# open-bldc.net
KiCad netlist of a schematic drawn in EAGLE
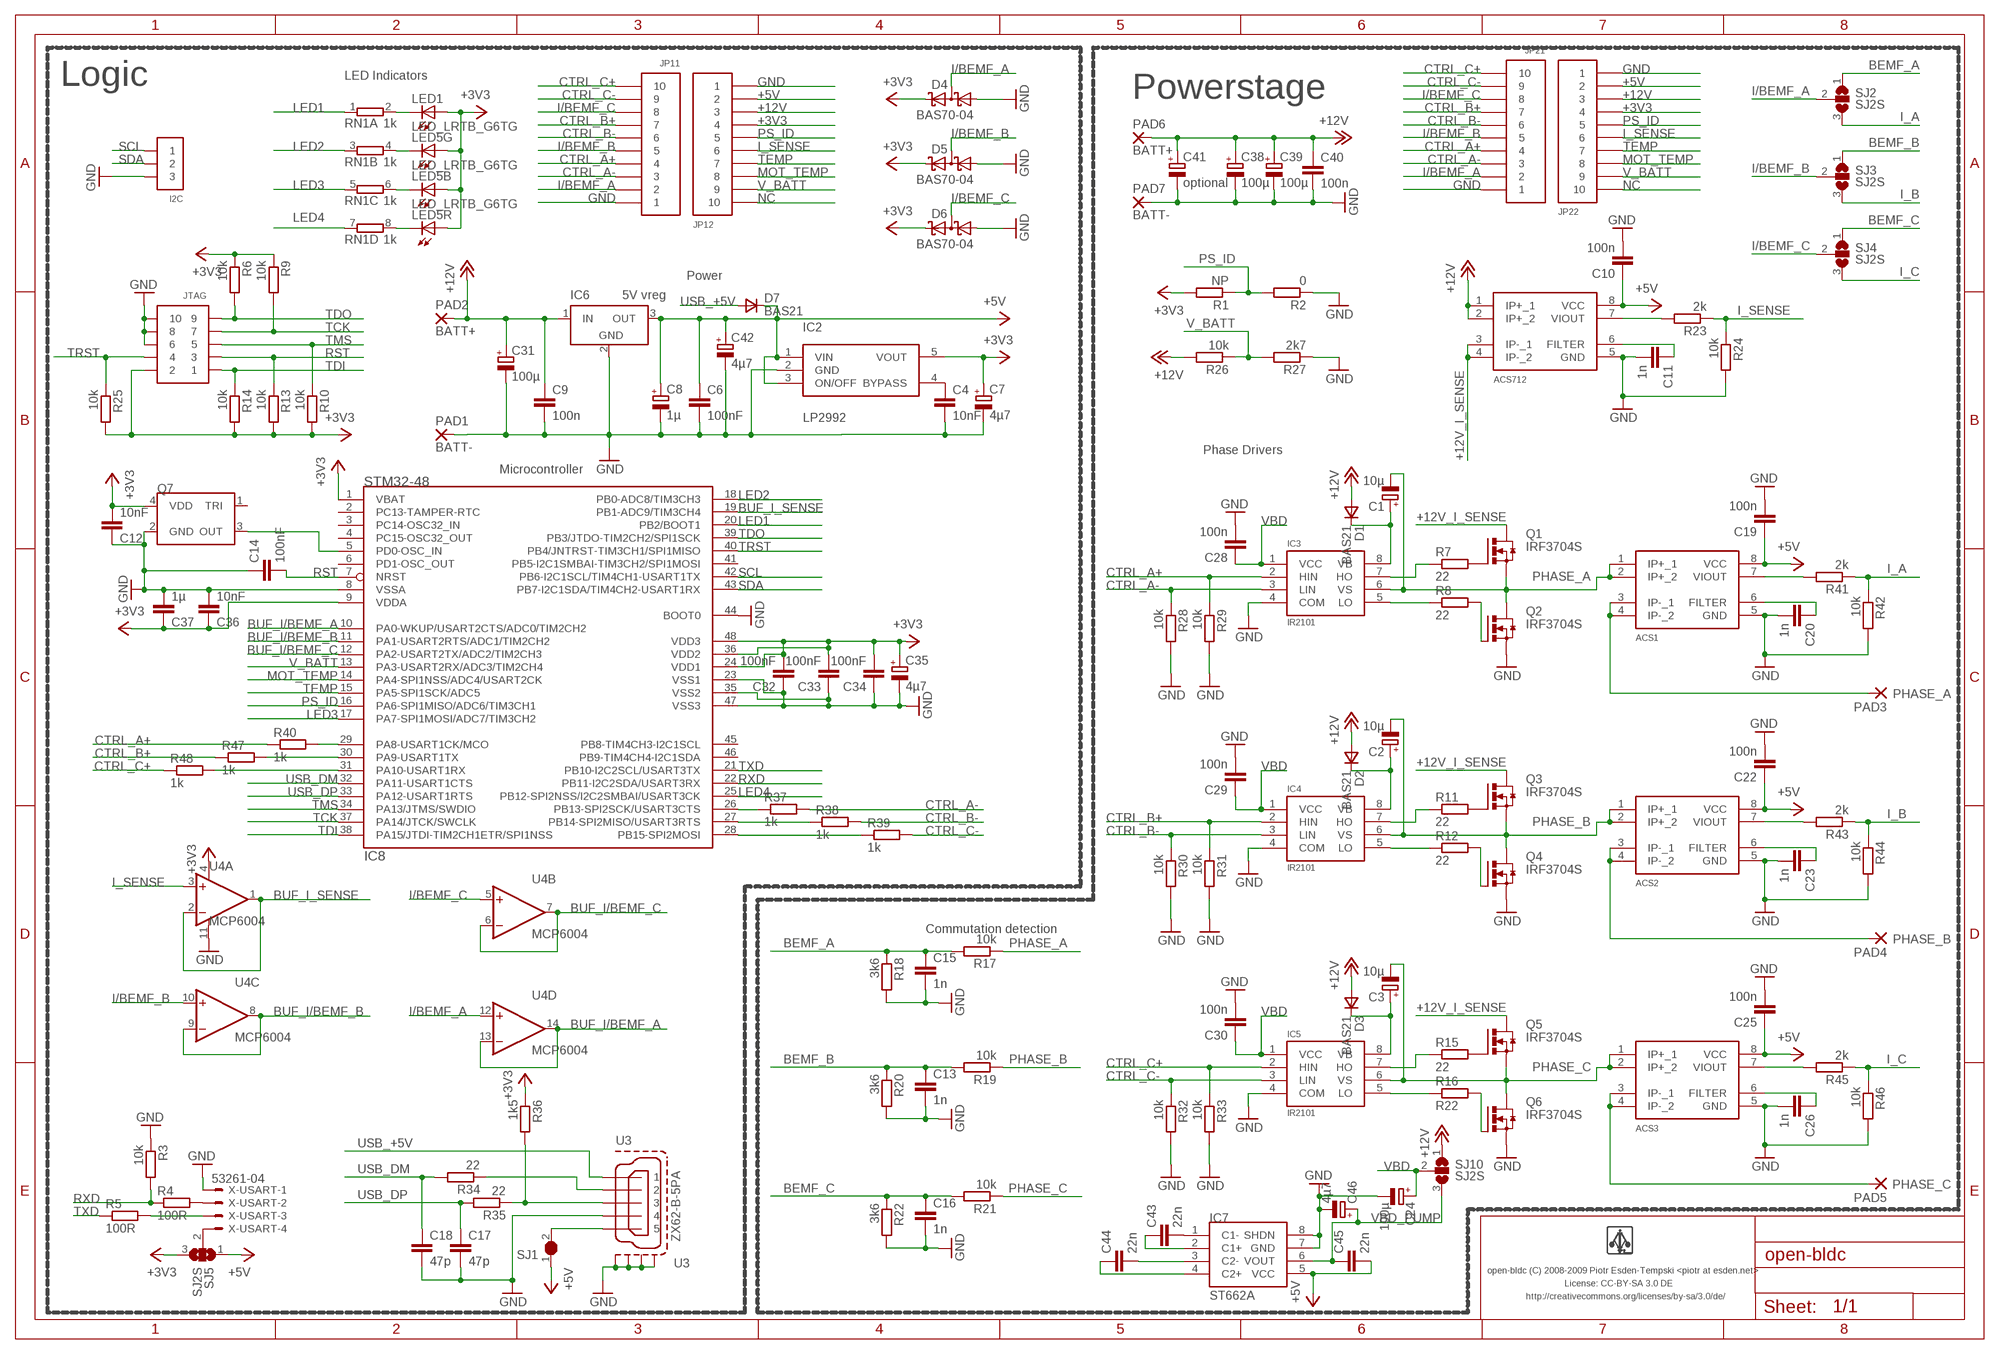
[diagram p0: schematic, sheet 1]

(export (version "E")
  (design (tool "Eeschema 10.0.6"))
  (components
    (comp (ref "ACS1")
      (value "ACS712")
      (footprint "eagle-import:SO8")
      (libsource (lib "eagle-import") (part "ACS712"))
    )
    (comp (ref "ACS2")
      (value "ACS712")
      (footprint "eagle-import:SO8")
      (libsource (lib "eagle-import") (part "ACS712"))
    )
    (comp (ref "ACS3")
      (value "ACS712")
      (footprint "eagle-import:SO8")
      (libsource (lib "eagle-import") (part "ACS712"))
    )
    (comp (ref "ACS712")
      (value "ACS712")
      (footprint "eagle-import:SO8")
      (libsource (lib "eagle-import") (part "ACS712"))
    )
    (comp (ref "C1")
      (value "10µ")
      (footprint "eagle-import:A_3216-18R")
      (libsource (lib "eagle-import") (part "CPOL-EUA/3216-18R"))
    )
    (comp (ref "C2")
      (value "10µ")
      (footprint "eagle-import:A_3216-18R")
      (libsource (lib "eagle-import") (part "CPOL-EUA/3216-18R"))
    )
    (comp (ref "C3")
      (value "10µ")
      (footprint "eagle-import:A_3216-18R")
      (libsource (lib "eagle-import") (part "CPOL-EUA/3216-18R"))
    )
    (comp (ref "C4")
      (value "10nF")
      (footprint "eagle-import:C0603")
      (libsource (lib "eagle-import") (part "C-EUC0603"))
    )
    (comp (ref "C6")
      (value "100nF")
      (footprint "eagle-import:C0603")
      (libsource (lib "eagle-import") (part "C-EUC0603"))
    )
    (comp (ref "C7")
      (value "4µ7")
      (footprint "eagle-import:A_3216-18R")
      (libsource (lib "eagle-import") (part "CPOL-EUA/3216-18R"))
    )
    (comp (ref "C8")
      (value "1µ")
      (footprint "eagle-import:A_3216-18R")
      (libsource (lib "eagle-import") (part "CPOL-EUA/3216-18R"))
    )
    (comp (ref "C9")
      (value "100n")
      (footprint "eagle-import:C0603")
      (libsource (lib "eagle-import") (part "C-EUC0603"))
    )
    (comp (ref "C10")
      (value "100n")
      (footprint "eagle-import:C0603")
      (libsource (lib "eagle-import") (part "C-EUC0603"))
    )
    (comp (ref "C11")
      (value "1n")
      (footprint "eagle-import:C0603")
      (libsource (lib "eagle-import") (part "C-EUC0603"))
    )
    (comp (ref "C12")
      (value "10nF")
      (footprint "eagle-import:C0603")
      (libsource (lib "eagle-import") (part "C-EUC0603"))
    )
    (comp (ref "C13")
      (value "1n")
      (footprint "eagle-import:C0603")
      (libsource (lib "eagle-import") (part "C-EUC0603"))
    )
    (comp (ref "C14")
      (value "100nF")
      (footprint "eagle-import:C0603")
      (libsource (lib "eagle-import") (part "C-EUC0603"))
    )
    (comp (ref "C15")
      (value "1n")
      (footprint "eagle-import:C0603")
      (libsource (lib "eagle-import") (part "C-EUC0603"))
    )
    (comp (ref "C16")
      (value "1n")
      (footprint "eagle-import:C0603")
      (libsource (lib "eagle-import") (part "C-EUC0603"))
    )
    (comp (ref "C17")
      (value "47p")
      (footprint "eagle-import:C0603")
      (libsource (lib "eagle-import") (part "C-EUC0603"))
    )
    (comp (ref "C18")
      (value "47p")
      (footprint "eagle-import:C0603")
      (libsource (lib "eagle-import") (part "C-EUC0603"))
    )
    (comp (ref "C19")
      (value "100n")
      (footprint "eagle-import:C0603")
      (libsource (lib "eagle-import") (part "C-EUC0603"))
    )
    (comp (ref "C20")
      (value "1n")
      (footprint "eagle-import:C0603")
      (libsource (lib "eagle-import") (part "C-EUC0603"))
    )
    (comp (ref "C22")
      (value "100n")
      (footprint "eagle-import:C0603")
      (libsource (lib "eagle-import") (part "C-EUC0603"))
    )
    (comp (ref "C23")
      (value "1n")
      (footprint "eagle-import:C0603")
      (libsource (lib "eagle-import") (part "C-EUC0603"))
    )
    (comp (ref "C24")
      (value "100µ")
      (footprint "eagle-import:D_7343-31R")
      (libsource (lib "eagle-import") (part "CPOL-EUD/7343-31R"))
    )
    (comp (ref "C25")
      (value "100n")
      (footprint "eagle-import:C0603")
      (libsource (lib "eagle-import") (part "C-EUC0603"))
    )
    (comp (ref "C26")
      (value "1n")
      (footprint "eagle-import:C0603")
      (libsource (lib "eagle-import") (part "C-EUC0603"))
    )
    (comp (ref "C28")
      (value "100n")
      (footprint "eagle-import:C0603")
      (libsource (lib "eagle-import") (part "C-EUC0603"))
    )
    (comp (ref "C29")
      (value "100n")
      (footprint "eagle-import:C0603")
      (libsource (lib "eagle-import") (part "C-EUC0603"))
    )
    (comp (ref "C30")
      (value "100n")
      (footprint "eagle-import:C0603")
      (libsource (lib "eagle-import") (part "C-EUC0603"))
    )
    (comp (ref "C31")
      (value "100µ")
      (footprint "eagle-import:D_7343-31R")
      (libsource (lib "eagle-import") (part "CPOL-EUD/7343-31R"))
    )
    (comp (ref "C32")
      (value "100nF")
      (footprint "eagle-import:C0603")
      (libsource (lib "eagle-import") (part "C-EUC0603"))
    )
    (comp (ref "C33")
      (value "100nF")
      (footprint "eagle-import:C0603")
      (libsource (lib "eagle-import") (part "C-EUC0603"))
    )
    (comp (ref "C34")
      (value "100nF")
      (footprint "eagle-import:C0603")
      (libsource (lib "eagle-import") (part "C-EUC0603"))
    )
    (comp (ref "C35")
      (value "4µ7")
      (footprint "eagle-import:A_3216-18R")
      (libsource (lib "eagle-import") (part "CPOL-EUA/3216-18R"))
    )
    (comp (ref "C36")
      (value "10nF")
      (footprint "eagle-import:C0603")
      (libsource (lib "eagle-import") (part "C-EUC0603"))
    )
    (comp (ref "C37")
      (value "1µ")
      (footprint "eagle-import:C0603")
      (libsource (lib "eagle-import") (part "C-EUC0603"))
    )
    (comp (ref "C38")
      (value "100µ")
      (footprint "eagle-import:D_7343-31R")
      (libsource (lib "eagle-import") (part "CPOL-EUD/7343-31R"))
    )
    (comp (ref "C39")
      (value "100µ")
      (footprint "eagle-import:D_7343-31R")
      (libsource (lib "eagle-import") (part "CPOL-EUD/7343-31R"))
    )
    (comp (ref "C40")
      (value "100n")
      (footprint "eagle-import:C0603")
      (libsource (lib "eagle-import") (part "C-EUC0603"))
    )
    (comp (ref "C41")
      (value "optional")
      (footprint "eagle-import:E5-6")
      (libsource (lib "eagle-import") (part "CPOL-EUE5-6"))
    )
    (comp (ref "C42")
      (value "4µ7")
      (footprint "eagle-import:A_3216-18R")
      (libsource (lib "eagle-import") (part "CPOL-EUA/3216-18R"))
    )
    (comp (ref "C43")
      (value "22n")
      (footprint "eagle-import:C0603")
      (libsource (lib "eagle-import") (part "C-EUC0603"))
    )
    (comp (ref "C44")
      (value "22n")
      (footprint "eagle-import:C0603")
      (libsource (lib "eagle-import") (part "C-EUC0603"))
    )
    (comp (ref "C45")
      (value "22n")
      (footprint "eagle-import:C0603")
      (libsource (lib "eagle-import") (part "C-EUC0603"))
    )
    (comp (ref "C46")
      (value "4µ7")
      (footprint "eagle-import:A_3216-18R")
      (libsource (lib "eagle-import") (part "CPOL-EUA/3216-18R"))
    )
    (comp (ref "D1")
      (value "BAS21")
      (footprint "eagle-import:SOT-23")
      (libsource (lib "eagle-import") (part "VAR2SOT23"))
    )
    (comp (ref "D2")
      (value "BAS21")
      (footprint "eagle-import:SOT-23")
      (libsource (lib "eagle-import") (part "VAR2SOT23"))
    )
    (comp (ref "D3")
      (value "BAS21")
      (footprint "eagle-import:SOT-23")
      (libsource (lib "eagle-import") (part "VAR2SOT23"))
    )
    (comp (ref "D4")
      (value "BAS70-04")
      (footprint "eagle-import:SOT23")
      (libsource (lib "eagle-import") (part "BAS70-04"))
    )
    (comp (ref "D5")
      (value "BAS70-04")
      (footprint "eagle-import:SOT23")
      (libsource (lib "eagle-import") (part "BAS70-04"))
    )
    (comp (ref "D6")
      (value "BAS70-04")
      (footprint "eagle-import:SOT23")
      (libsource (lib "eagle-import") (part "BAS70-04"))
    )
    (comp (ref "D7")
      (value "BAS21")
      (footprint "eagle-import:SOT-23")
      (libsource (lib "eagle-import") (part "VAR2SOT23"))
    )
    (comp (ref "I2C")
      (value "PIN_HDR_EDG_1.27MM_3-1")
      (footprint "eagle-import:PIN_HDR_EDG_1.27MM_3-1")
      (libsource (lib "eagle-import") (part "PIN_HDR_EDG_1.27MM_3-1"))
    )
    (comp (ref "IC2")
      (value "LP2992")
      (footprint "eagle-import:SOT23-5")
      (libsource (lib "eagle-import") (part "LP2992"))
    )
    (comp (ref "IC3")
      (value "IR2101")
      (footprint "eagle-import:SO-8")
      (libsource (lib "eagle-import") (part "IR2101"))
    )
    (comp (ref "IC4")
      (value "IR2101")
      (footprint "eagle-import:SO-8")
      (libsource (lib "eagle-import") (part "IR2101"))
    )
    (comp (ref "IC5")
      (value "IR2101")
      (footprint "eagle-import:SO-8")
      (libsource (lib "eagle-import") (part "IR2101"))
    )
    (comp (ref "IC6")
      (value "5V vreg")
      (footprint "eagle-import:SOT223")
      (libsource (lib "eagle-import") (part "LT1129CST5"))
    )
    (comp (ref "IC7")
      (value "ST662A")
      (footprint "eagle-import:SO8")
      (libsource (lib "eagle-import") (part "ST662A"))
    )
    (comp (ref "IC8")
      (value "STM32-48")
      (footprint "eagle-import:LQFP48")
      (libsource (lib "eagle-import") (part "STM32-48"))
    )
    (comp (ref "JP11")
      (value "PIN_HDR_1.27MM_10")
      (footprint "eagle-import:PIN_HDR_1.27MM_10")
      (libsource (lib "eagle-import") (part "PIN_HDR_1.27MM_10_TH"))
    )
    (comp (ref "JP12")
      (value "PIN_HDR_1.27MM_10")
      (footprint "eagle-import:PIN_HDR_1.27MM_10")
      (libsource (lib "eagle-import") (part "PIN_HDR_1.27MM_10_TH"))
    )
    (comp (ref "JP21")
      (value "PIN_HDR_1.27MM_10")
      (footprint "eagle-import:PIN_HDR_1.27MM_10")
      (libsource (lib "eagle-import") (part "PIN_HDR_1.27MM_10_TH"))
    )
    (comp (ref "JP22")
      (value "PIN_HDR_1.27MM_10")
      (footprint "eagle-import:PIN_HDR_1.27MM_10")
      (libsource (lib "eagle-import") (part "PIN_HDR_1.27MM_10_TH"))
    )
    (comp (ref "JTAG")
      (value "PIN_HDR_EDG_1.27MM_5-2")
      (footprint "eagle-import:PIN_HDR_EDG_1.27MM_5-2")
      (libsource (lib "eagle-import") (part "PIN_HDR_EDG_1.27MM_5-2"))
    )
    (comp (ref "LED1")
      (value "AMBER")
      (footprint "eagle-import:CHIP-LED0603")
      (libsource (lib "eagle-import") (part "LEDCHIP-LED0603"))
    )
    (comp (ref "LED5")
      (value "LED_LRTB_G6TG")
      (footprint "eagle-import:PLCC6")
      (libsource (lib "eagle-import") (part "LED_LRTB_G6TG"))
    )
    (comp (ref "PAD1")
      (value "BATT-")
      (footprint "eagle-import:SMD2,54-5,08")
      (libsource (lib "eagle-import") (part "SMD5"))
    )
    (comp (ref "PAD2")
      (value "BATT+")
      (footprint "eagle-import:SMD2,54-5,08")
      (libsource (lib "eagle-import") (part "SMD5"))
    )
    (comp (ref "PAD3")
      (value "PHASE_A")
      (footprint "eagle-import:SMD2,54-5,08")
      (libsource (lib "eagle-import") (part "SMD5"))
    )
    (comp (ref "PAD4")
      (value "PHASE_B")
      (footprint "eagle-import:SMD2,54-5,08")
      (libsource (lib "eagle-import") (part "SMD5"))
    )
    (comp (ref "PAD5")
      (value "PHASE_C")
      (footprint "eagle-import:SMD2,54-5,08")
      (libsource (lib "eagle-import") (part "SMD5"))
    )
    (comp (ref "PAD6")
      (value "BATT+")
      (footprint "eagle-import:SMD2,54-5,08")
      (libsource (lib "eagle-import") (part "SMD5"))
    )
    (comp (ref "PAD7")
      (value "BATT-")
      (footprint "eagle-import:SMD2,54-5,08")
      (libsource (lib "eagle-import") (part "SMD5"))
    )
    (comp (ref "Q1")
      (value "IRF3704S")
      (footprint "eagle-import:D2PACK")
      (libsource (lib "eagle-import") (part "IRF3704S"))
    )
    (comp (ref "Q2")
      (value "IRF3704S")
      (footprint "eagle-import:D2PACK")
      (libsource (lib "eagle-import") (part "IRF3704S"))
    )
    (comp (ref "Q3")
      (value "IRF3704S")
      (footprint "eagle-import:D2PACK")
      (libsource (lib "eagle-import") (part "IRF3704S"))
    )
    (comp (ref "Q4")
      (value "IRF3704S")
      (footprint "eagle-import:D2PACK")
      (libsource (lib "eagle-import") (part "IRF3704S"))
    )
    (comp (ref "Q5")
      (value "IRF3704S")
      (footprint "eagle-import:D2PACK")
      (libsource (lib "eagle-import") (part "IRF3704S"))
    )
    (comp (ref "Q6")
      (value "IRF3704S")
      (footprint "eagle-import:D2PACK")
      (libsource (lib "eagle-import") (part "IRF3704S"))
    )
    (comp (ref "Q7")
      (value "ASE_ASCILLATOR")
      (footprint "eagle-import:ASE_OSCILLATOR")
      (libsource (lib "eagle-import") (part "ASE_ASCILLATOR"))
    )
    (comp (ref "R1")
      (value "NP")
      (footprint "eagle-import:R0603")
      (libsource (lib "eagle-import") (part "R-EU_R0603"))
    )
    (comp (ref "R2")
      (value "0")
      (footprint "eagle-import:R0603")
      (libsource (lib "eagle-import") (part "R-EU_R0603"))
    )
    (comp (ref "R3")
      (value "10k")
      (footprint "eagle-import:R0603")
      (libsource (lib "eagle-import") (part "R-EU_R0603"))
    )
    (comp (ref "R4")
      (value "100R")
      (footprint "eagle-import:R0603")
      (libsource (lib "eagle-import") (part "R-EU_R0603"))
    )
    (comp (ref "R5")
      (value "100R")
      (footprint "eagle-import:R0603")
      (libsource (lib "eagle-import") (part "R-EU_R0603"))
    )
    (comp (ref "R6")
      (value "10k")
      (footprint "eagle-import:R0603")
      (libsource (lib "eagle-import") (part "R-EU_R0603"))
    )
    (comp (ref "R7")
      (value "22")
      (footprint "eagle-import:R0603")
      (libsource (lib "eagle-import") (part "R-EU_R0603"))
    )
    (comp (ref "R8")
      (value "22")
      (footprint "eagle-import:R0603")
      (libsource (lib "eagle-import") (part "R-EU_R0603"))
    )
    (comp (ref "R9")
      (value "10k")
      (footprint "eagle-import:R0603")
      (libsource (lib "eagle-import") (part "R-EU_R0603"))
    )
    (comp (ref "R10")
      (value "10k")
      (footprint "eagle-import:R0603")
      (libsource (lib "eagle-import") (part "R-EU_R0603"))
    )
    (comp (ref "R11")
      (value "22")
      (footprint "eagle-import:R0603")
      (libsource (lib "eagle-import") (part "R-EU_R0603"))
    )
    (comp (ref "R12")
      (value "22")
      (footprint "eagle-import:R0603")
      (libsource (lib "eagle-import") (part "R-EU_R0603"))
    )
    (comp (ref "R13")
      (value "10k")
      (footprint "eagle-import:R0603")
      (libsource (lib "eagle-import") (part "R-EU_R0603"))
    )
    (comp (ref "R14")
      (value "10k")
      (footprint "eagle-import:R0603")
      (libsource (lib "eagle-import") (part "R-EU_R0603"))
    )
    (comp (ref "R15")
      (value "22")
      (footprint "eagle-import:R0603")
      (libsource (lib "eagle-import") (part "R-EU_R0603"))
    )
    (comp (ref "R16")
      (value "R22")
      (footprint "eagle-import:R0603")
      (libsource (lib "eagle-import") (part "R-EU_R0603"))
    )
    (comp (ref "R17")
      (value "10k")
      (footprint "eagle-import:R0603")
      (libsource (lib "eagle-import") (part "R-EU_R0603"))
    )
    (comp (ref "R18")
      (value "3k6")
      (footprint "eagle-import:R0603")
      (libsource (lib "eagle-import") (part "R-EU_R0603"))
    )
    (comp (ref "R19")
      (value "10k")
      (footprint "eagle-import:R0603")
      (libsource (lib "eagle-import") (part "R-EU_R0603"))
    )
    (comp (ref "R20")
      (value "3k6")
      (footprint "eagle-import:R0603")
      (libsource (lib "eagle-import") (part "R-EU_R0603"))
    )
    (comp (ref "R21")
      (value "10k")
      (footprint "eagle-import:R0603")
      (libsource (lib "eagle-import") (part "R-EU_R0603"))
    )
    (comp (ref "R22")
      (value "3k6")
      (footprint "eagle-import:R0603")
      (libsource (lib "eagle-import") (part "R-EU_R0603"))
    )
    (comp (ref "R23")
      (value "2k")
      (footprint "eagle-import:R0603")
      (libsource (lib "eagle-import") (part "R-EU_R0603"))
    )
    (comp (ref "R24")
      (value "10k")
      (footprint "eagle-import:R0603")
      (libsource (lib "eagle-import") (part "R-EU_R0603"))
    )
    (comp (ref "R25")
      (value "10k")
      (footprint "eagle-import:R0603")
      (libsource (lib "eagle-import") (part "R-EU_R0603"))
    )
    (comp (ref "R26")
      (value "10k")
      (footprint "eagle-import:R0603")
      (libsource (lib "eagle-import") (part "R-EU_R0603"))
    )
    (comp (ref "R27")
      (value "2k7")
      (footprint "eagle-import:R0603")
      (libsource (lib "eagle-import") (part "R-EU_R0603"))
    )
    (comp (ref "R28")
      (value "10k")
      (footprint "eagle-import:R0603")
      (libsource (lib "eagle-import") (part "R-EU_R0603"))
    )
    (comp (ref "R29")
      (value "10k")
      (footprint "eagle-import:R0603")
      (libsource (lib "eagle-import") (part "R-EU_R0603"))
    )
    (comp (ref "R30")
      (value "10k")
      (footprint "eagle-import:R0603")
      (libsource (lib "eagle-import") (part "R-EU_R0603"))
    )
    (comp (ref "R31")
      (value "10k")
      (footprint "eagle-import:R0603")
      (libsource (lib "eagle-import") (part "R-EU_R0603"))
    )
    (comp (ref "R32")
      (value "10k")
      (footprint "eagle-import:R0603")
      (libsource (lib "eagle-import") (part "R-EU_R0603"))
    )
    (comp (ref "R33")
      (value "10k")
      (footprint "eagle-import:R0603")
      (libsource (lib "eagle-import") (part "R-EU_R0603"))
    )
    (comp (ref "R34")
      (value "22")
      (footprint "eagle-import:R0603")
      (libsource (lib "eagle-import") (part "R-EU_R0603"))
    )
    (comp (ref "R35")
      (value "22")
      (footprint "eagle-import:R0603")
      (libsource (lib "eagle-import") (part "R-EU_R0603"))
    )
    (comp (ref "R36")
      (value "1k5")
      (footprint "eagle-import:R0603")
      (libsource (lib "eagle-import") (part "R-EU_R0603"))
    )
    (comp (ref "R37")
      (value "1k")
      (footprint "eagle-import:R0603")
      (libsource (lib "eagle-import") (part "R-EU_R0603"))
    )
    (comp (ref "R38")
      (value "1k")
      (footprint "eagle-import:R0603")
      (libsource (lib "eagle-import") (part "R-EU_R0603"))
    )
    (comp (ref "R39")
      (value "1k")
      (footprint "eagle-import:R0603")
      (libsource (lib "eagle-import") (part "R-EU_R0603"))
    )
    (comp (ref "R40")
      (value "1k")
      (footprint "eagle-import:R0603")
      (libsource (lib "eagle-import") (part "R-EU_R0603"))
    )
    (comp (ref "R41")
      (value "2k")
      (footprint "eagle-import:R0603")
      (libsource (lib "eagle-import") (part "R-EU_R0603"))
    )
    (comp (ref "R42")
      (value "10k")
      (footprint "eagle-import:R0603")
      (libsource (lib "eagle-import") (part "R-EU_R0603"))
    )
    (comp (ref "R43")
      (value "2k")
      (footprint "eagle-import:R0603")
      (libsource (lib "eagle-import") (part "R-EU_R0603"))
    )
    (comp (ref "R44")
      (value "10k")
      (footprint "eagle-import:R0603")
      (libsource (lib "eagle-import") (part "R-EU_R0603"))
    )
    (comp (ref "R45")
      (value "2k")
      (footprint "eagle-import:R0603")
      (libsource (lib "eagle-import") (part "R-EU_R0603"))
    )
    (comp (ref "R46")
      (value "10k")
      (footprint "eagle-import:R0603")
      (libsource (lib "eagle-import") (part "R-EU_R0603"))
    )
    (comp (ref "R47")
      (value "1k")
      (footprint "eagle-import:R0603")
      (libsource (lib "eagle-import") (part "R-EU_R0603"))
    )
    (comp (ref "R48")
      (value "1k")
      (footprint "eagle-import:R0603")
      (libsource (lib "eagle-import") (part "R-EU_R0603"))
    )
    (comp (ref "RN1")
      (value "1k")
      (footprint "eagle-import:R4N1206")
      (libsource (lib "eagle-import") (part "R4N1206"))
    )
    (comp (ref "SJ1")
      (value "SJ1S")
      (footprint "eagle-import:SJ1S")
      (libsource (lib "eagle-import") (part "SJ1S"))
    )
    (comp (ref "SJ2")
      (value "SJ2S")
      (footprint "eagle-import:SJ2S")
      (libsource (lib "eagle-import") (part "SJ2S"))
    )
    (comp (ref "SJ3")
      (value "SJ2S")
      (footprint "eagle-import:SJ2S")
      (libsource (lib "eagle-import") (part "SJ2S"))
    )
    (comp (ref "SJ4")
      (value "SJ2S")
      (footprint "eagle-import:SJ2S")
      (libsource (lib "eagle-import") (part "SJ2S"))
    )
    (comp (ref "SJ5")
      (value "SJ2S")
      (footprint "eagle-import:SJ2S")
      (libsource (lib "eagle-import") (part "SJ2S"))
    )
    (comp (ref "SJ10")
      (value "SJ2S")
      (footprint "eagle-import:SJ2S")
      (libsource (lib "eagle-import") (part "SJ2S"))
    )
    (comp (ref "U3")
      (value "ZX62-B-5PA")
      (footprint "eagle-import:ZX62-B-5PA")
      (libsource (lib "eagle-import") (part "ZX62-B-5PA"))
    )
    (comp (ref "U4")
      (value "MCP6004")
      (footprint "eagle-import:TSSOP_14")
      (libsource (lib "eagle-import") (part "MCP6004"))
    )
    (comp (ref "X-USART")
      (value "53261-04")
      (footprint "eagle-import:53261-04")
      (libsource (lib "eagle-import") (part "53?-04261"))
    )
  )
  (nets
    (net (code "1") (name "+3V3") (class "Default")
      (node (ref "C12") (pin "2") (pinfunction "2_2") (pintype "passive"))
      (node (ref "C32") (pin "2") (pinfunction "2_2") (pintype "passive"))
      (node (ref "C33") (pin "2") (pinfunction "2_2") (pintype "passive"))
      (node (ref "C34") (pin "2") (pinfunction "2_2") (pintype "passive"))
      (node (ref "C35") (pin "+") (pinfunction "+_+") (pintype "passive"))
      (node (ref "C36") (pin "1") (pinfunction "1_1") (pintype "passive"))
      (node (ref "C37") (pin "1") (pinfunction "1_1") (pintype "passive"))
      (node (ref "C7") (pin "+") (pinfunction "+_+") (pintype "passive"))
      (node (ref "D4") (pin "2") (pinfunction "C2_2") (pintype "passive"))
      (node (ref "D5") (pin "2") (pinfunction "C2_2") (pintype "passive"))
      (node (ref "D6") (pin "2") (pinfunction "C2_2") (pintype "passive"))
      (node (ref "IC2") (pin "5") (pinfunction "VOUT_5") (pintype "bidirectional"))
      (node (ref "IC8") (pin "1") (pinfunction "VBAT_1") (pintype "power_in"))
      (node (ref "IC8") (pin "24") (pinfunction "VDD1_24") (pintype "power_in"))
      (node (ref "IC8") (pin "36") (pinfunction "VDD2_36") (pintype "power_in"))
      (node (ref "IC8") (pin "48") (pinfunction "VDD3_48") (pintype "power_in"))
      (node (ref "IC8") (pin "9") (pinfunction "VDDA_9") (pintype "power_in"))
      (node (ref "JP12") (pin "P$4") (pinfunction "4_P$4") (pintype "bidirectional"))
      (node (ref "JP22") (pin "P$4") (pinfunction "4_P$4") (pintype "bidirectional"))
      (node (ref "JTAG") (pin "P$2") (pinfunction "2_P$2") (pintype "bidirectional"))
      (node (ref "LED1") (pin "A") (pinfunction "A_A") (pintype "passive"))
      (node (ref "LED5") (pin "A1") (pinfunction "A_A1") (pintype "passive"))
      (node (ref "LED5") (pin "A2") (pinfunction "A_A2") (pintype "passive"))
      (node (ref "LED5") (pin "A3") (pinfunction "A_A3") (pintype "passive"))
      (node (ref "Q7") (pin "4") (pinfunction "VDD_4") (pintype "power_in"))
      (node (ref "R1") (pin "2") (pinfunction "2_2") (pintype "passive"))
      (node (ref "R10") (pin "2") (pinfunction "2_2") (pintype "passive"))
      (node (ref "R13") (pin "2") (pinfunction "2_2") (pintype "passive"))
      (node (ref "R14") (pin "2") (pinfunction "2_2") (pintype "passive"))
      (node (ref "R25") (pin "2") (pinfunction "2_2") (pintype "passive"))
      (node (ref "R36") (pin "1") (pinfunction "1_1") (pintype "passive"))
      (node (ref "R6") (pin "1") (pinfunction "1_1") (pintype "passive"))
      (node (ref "R9") (pin "1") (pinfunction "1_1") (pintype "passive"))
      (node (ref "SJ5") (pin "3") (pinfunction "3_3") (pintype "passive"))
      (node (ref "U4") (pin "4") (pinfunction "V+_4") (pintype "power_in"))
    )
    (net (code "2") (name "+5V") (class "Default")
      (node (ref "ACS1") (pin "8") (pinfunction "VCC_8") (pintype "bidirectional"))
      (node (ref "ACS2") (pin "8") (pinfunction "VCC_8") (pintype "bidirectional"))
      (node (ref "ACS3") (pin "8") (pinfunction "VCC_8") (pintype "bidirectional"))
      (node (ref "ACS712") (pin "8") (pinfunction "VCC_8") (pintype "bidirectional"))
      (node (ref "C10") (pin "1") (pinfunction "1_1") (pintype "passive"))
      (node (ref "C19") (pin "1") (pinfunction "1_1") (pintype "passive"))
      (node (ref "C22") (pin "1") (pinfunction "1_1") (pintype "passive"))
      (node (ref "C25") (pin "1") (pinfunction "1_1") (pintype "passive"))
      (node (ref "C42") (pin "+") (pinfunction "+_+") (pintype "passive"))
      (node (ref "C45") (pin "2") (pinfunction "2_2") (pintype "passive"))
      (node (ref "C6") (pin "1") (pinfunction "1_1") (pintype "passive"))
      (node (ref "C8") (pin "+") (pinfunction "+_+") (pintype "passive"))
      (node (ref "D7") (pin "1") (pinfunction "C_1") (pintype "passive"))
      (node (ref "IC2") (pin "1") (pinfunction "VIN_1") (pintype "bidirectional"))
      (node (ref "IC2") (pin "3") (pinfunction "ON/OFF_3") (pintype "bidirectional"))
      (node (ref "IC6") (pin "3") (pinfunction "OUT_3") (pintype "power_in"))
      (node (ref "IC7") (pin "5") (pinfunction "VCC_5") (pintype "bidirectional"))
      (node (ref "JP12") (pin "P$2") (pinfunction "2_P$2") (pintype "bidirectional"))
      (node (ref "JP22") (pin "P$2") (pinfunction "2_P$2") (pintype "bidirectional"))
      (node (ref "SJ1") (pin "1") (pinfunction "1_1") (pintype "passive"))
      (node (ref "SJ5") (pin "1") (pinfunction "1_1") (pintype "passive"))
    )
    (net (code "3") (name "+12V") (class "Default")
      (node (ref "ACS712") (pin "1") (pinfunction "IP+_1_1") (pintype "bidirectional"))
      (node (ref "ACS712") (pin "2") (pinfunction "IP+_2_2") (pintype "bidirectional"))
      (node (ref "C31") (pin "+") (pinfunction "+_+") (pintype "passive"))
      (node (ref "C38") (pin "+") (pinfunction "+_+") (pintype "passive"))
      (node (ref "C39") (pin "+") (pinfunction "+_+") (pintype "passive"))
      (node (ref "C40") (pin "1") (pinfunction "1_1") (pintype "passive"))
      (node (ref "C41") (pin "+") (pinfunction "+_+") (pintype "passive"))
      (node (ref "C9") (pin "1") (pinfunction "1_1") (pintype "passive"))
      (node (ref "D1") (pin "3") (pinfunction "A_3") (pintype "passive"))
      (node (ref "D2") (pin "3") (pinfunction "A_3") (pintype "passive"))
      (node (ref "D3") (pin "3") (pinfunction "A_3") (pintype "passive"))
      (node (ref "IC6") (pin "1") (pinfunction "IN_1") (pintype "input"))
      (node (ref "JP12") (pin "P$3") (pinfunction "3_P$3") (pintype "bidirectional"))
      (node (ref "JP22") (pin "P$3") (pinfunction "3_P$3") (pintype "bidirectional"))
      (node (ref "PAD2") (pin "1") (pinfunction "P_1") (pintype "passive"))
      (node (ref "PAD6") (pin "1") (pinfunction "P_1") (pintype "passive"))
      (node (ref "R26") (pin "2") (pinfunction "2_2") (pintype "passive"))
      (node (ref "SJ10") (pin "1") (pinfunction "1_1") (pintype "passive"))
    )
    (net (code "4") (name "/+12V_I_SENSE") (class "Default")
      (node (ref "ACS712") (pin "3") (pinfunction "IP-_1_3") (pintype "bidirectional"))
      (node (ref "ACS712") (pin "4") (pinfunction "IP-_2_4") (pintype "bidirectional"))
      (node (ref "Q1") (pin "2") (pinfunction "D_2") (pintype "passive"))
      (node (ref "Q3") (pin "2") (pinfunction "D_2") (pintype "passive"))
      (node (ref "Q5") (pin "2") (pinfunction "D_2") (pintype "passive"))
    )
    (net (code "5") (name "/BEMF_A") (class "Default")
      (node (ref "C15") (pin "1") (pinfunction "1_1") (pintype "passive"))
      (node (ref "R17") (pin "2") (pinfunction "2_2") (pintype "passive"))
      (node (ref "R18") (pin "1") (pinfunction "1_1") (pintype "passive"))
      (node (ref "SJ2") (pin "1") (pinfunction "1_1") (pintype "passive"))
    )
    (net (code "6") (name "/BEMF_B") (class "Default")
      (node (ref "C13") (pin "1") (pinfunction "1_1") (pintype "passive"))
      (node (ref "R19") (pin "2") (pinfunction "2_2") (pintype "passive"))
      (node (ref "R20") (pin "1") (pinfunction "1_1") (pintype "passive"))
      (node (ref "SJ3") (pin "1") (pinfunction "1_1") (pintype "passive"))
    )
    (net (code "7") (name "/BEMF_C") (class "Default")
      (node (ref "C16") (pin "1") (pinfunction "1_1") (pintype "passive"))
      (node (ref "R21") (pin "2") (pinfunction "2_2") (pintype "passive"))
      (node (ref "R22") (pin "1") (pinfunction "1_1") (pintype "passive"))
      (node (ref "SJ4") (pin "1") (pinfunction "1_1") (pintype "passive"))
    )
    (net (code "8") (name "/BUF_I_SENSE") (class "Default")
      (node (ref "IC8") (pin "19") (pinfunction "PB1-ADC9/TIM3CH4_19") (pintype "bidirectional"))
      (node (ref "U4") (pin "1") (pinfunction "OUT_1") (pintype "output"))
      (node (ref "U4") (pin "2") (pinfunction "-IN_2") (pintype "input"))
    )
    (net (code "9") (name "/BUF_I{slash}BEMF_A") (class "Default")
      (node (ref "IC8") (pin "10") (pinfunction "PA0-WKUP/USART2CTS/ADC0/TIM2CH2_10") (pintype "bidirectional"))
      (node (ref "U4") (pin "13") (pinfunction "-IN_13") (pintype "input"))
      (node (ref "U4") (pin "14") (pinfunction "OUT_14") (pintype "output"))
    )
    (net (code "10") (name "/BUF_I{slash}BEMF_B") (class "Default")
      (node (ref "IC8") (pin "11") (pinfunction "PA1-USART2RTS/ADC1/TIM2CH2_11") (pintype "bidirectional"))
      (node (ref "U4") (pin "8") (pinfunction "OUT_8") (pintype "output"))
      (node (ref "U4") (pin "9") (pinfunction "-IN_9") (pintype "input"))
    )
    (net (code "11") (name "/BUF_I{slash}BEMF_C") (class "Default")
      (node (ref "IC8") (pin "12") (pinfunction "PA2-USART2TX/ADC2/TIM2CH3_12") (pintype "bidirectional"))
      (node (ref "U4") (pin "6") (pinfunction "-IN_6") (pintype "input"))
      (node (ref "U4") (pin "7") (pinfunction "OUT_7") (pintype "output"))
    )
    (net (code "12") (name "/CTRL_A+") (class "Default")
      (node (ref "IC3") (pin "2") (pinfunction "HIN_2") (pintype "bidirectional"))
      (node (ref "JP11") (pin "P$4") (pinfunction "4_P$4") (pintype "bidirectional"))
      (node (ref "JP21") (pin "P$4") (pinfunction "4_P$4") (pintype "bidirectional"))
      (node (ref "R29") (pin "1") (pinfunction "1_1") (pintype "passive"))
      (node (ref "R40") (pin "1") (pinfunction "1_1") (pintype "passive"))
    )
    (net (code "13") (name "/CTRL_A-") (class "Default")
      (node (ref "IC3") (pin "3") (pinfunction "LIN_3") (pintype "bidirectional"))
      (node (ref "JP11") (pin "P$3") (pinfunction "3_P$3") (pintype "bidirectional"))
      (node (ref "JP21") (pin "P$3") (pinfunction "3_P$3") (pintype "bidirectional"))
      (node (ref "R28") (pin "1") (pinfunction "1_1") (pintype "passive"))
      (node (ref "R37") (pin "2") (pinfunction "2_2") (pintype "passive"))
    )
    (net (code "14") (name "/CTRL_B+") (class "Default")
      (node (ref "IC4") (pin "2") (pinfunction "HIN_2") (pintype "bidirectional"))
      (node (ref "JP11") (pin "P$7") (pinfunction "7_P$7") (pintype "bidirectional"))
      (node (ref "JP21") (pin "P$7") (pinfunction "7_P$7") (pintype "bidirectional"))
      (node (ref "R31") (pin "1") (pinfunction "1_1") (pintype "passive"))
      (node (ref "R47") (pin "1") (pinfunction "1_1") (pintype "passive"))
    )
    (net (code "15") (name "/CTRL_B-") (class "Default")
      (node (ref "IC4") (pin "3") (pinfunction "LIN_3") (pintype "bidirectional"))
      (node (ref "JP11") (pin "P$6") (pinfunction "6_P$6") (pintype "bidirectional"))
      (node (ref "JP21") (pin "P$6") (pinfunction "6_P$6") (pintype "bidirectional"))
      (node (ref "R30") (pin "1") (pinfunction "1_1") (pintype "passive"))
      (node (ref "R38") (pin "2") (pinfunction "2_2") (pintype "passive"))
    )
    (net (code "16") (name "/CTRL_C+") (class "Default")
      (node (ref "IC5") (pin "2") (pinfunction "HIN_2") (pintype "bidirectional"))
      (node (ref "JP11") (pin "P$10") (pinfunction "10_P$10") (pintype "bidirectional"))
      (node (ref "JP21") (pin "P$10") (pinfunction "10_P$10") (pintype "bidirectional"))
      (node (ref "R33") (pin "1") (pinfunction "1_1") (pintype "passive"))
      (node (ref "R48") (pin "1") (pinfunction "1_1") (pintype "passive"))
    )
    (net (code "17") (name "/CTRL_C-") (class "Default")
      (node (ref "IC5") (pin "3") (pinfunction "LIN_3") (pintype "bidirectional"))
      (node (ref "JP11") (pin "P$9") (pinfunction "9_P$9") (pintype "bidirectional"))
      (node (ref "JP21") (pin "P$9") (pinfunction "9_P$9") (pintype "bidirectional"))
      (node (ref "R32") (pin "1") (pinfunction "1_1") (pintype "passive"))
      (node (ref "R39") (pin "2") (pinfunction "2_2") (pintype "passive"))
    )
    (net (code "18") (name "/I_A") (class "Default")
      (node (ref "R41") (pin "1") (pinfunction "1_1") (pintype "passive"))
      (node (ref "R42") (pin "1") (pinfunction "1_1") (pintype "passive"))
      (node (ref "SJ2") (pin "3") (pinfunction "3_3") (pintype "passive"))
    )
    (net (code "19") (name "/I_B") (class "Default")
      (node (ref "R43") (pin "1") (pinfunction "1_1") (pintype "passive"))
      (node (ref "R44") (pin "1") (pinfunction "1_1") (pintype "passive"))
      (node (ref "SJ3") (pin "3") (pinfunction "3_3") (pintype "passive"))
    )
    (net (code "20") (name "/I_C") (class "Default")
      (node (ref "R45") (pin "1") (pinfunction "1_1") (pintype "passive"))
      (node (ref "R46") (pin "1") (pinfunction "1_1") (pintype "passive"))
      (node (ref "SJ4") (pin "3") (pinfunction "3_3") (pintype "passive"))
    )
    (net (code "21") (name "/I_SENSE") (class "Default")
      (node (ref "JP12") (pin "P$6") (pinfunction "6_P$6") (pintype "bidirectional"))
      (node (ref "JP22") (pin "P$6") (pinfunction "6_P$6") (pintype "bidirectional"))
      (node (ref "R23") (pin "1") (pinfunction "1_1") (pintype "passive"))
      (node (ref "R24") (pin "1") (pinfunction "1_1") (pintype "passive"))
      (node (ref "U4") (pin "3") (pinfunction "+IN_3") (pintype "input"))
    )
    (net (code "22") (name "/I{slash}BEMF_A") (class "Default")
      (node (ref "D4") (pin "3") (pinfunction "C1A2_3") (pintype "passive"))
      (node (ref "JP11") (pin "P$2") (pinfunction "2_P$2") (pintype "bidirectional"))
      (node (ref "JP21") (pin "P$2") (pinfunction "2_P$2") (pintype "bidirectional"))
      (node (ref "SJ2") (pin "2") (pinfunction "2_2") (pintype "passive"))
      (node (ref "U4") (pin "12") (pinfunction "+IN_12") (pintype "input"))
    )
    (net (code "23") (name "/I{slash}BEMF_B") (class "Default")
      (node (ref "D5") (pin "3") (pinfunction "C1A2_3") (pintype "passive"))
      (node (ref "JP11") (pin "P$5") (pinfunction "5_P$5") (pintype "bidirectional"))
      (node (ref "JP21") (pin "P$5") (pinfunction "5_P$5") (pintype "bidirectional"))
      (node (ref "SJ3") (pin "2") (pinfunction "2_2") (pintype "passive"))
      (node (ref "U4") (pin "10") (pinfunction "+IN_10") (pintype "input"))
    )
    (net (code "24") (name "/I{slash}BEMF_C") (class "Default")
      (node (ref "D6") (pin "3") (pinfunction "C1A2_3") (pintype "passive"))
      (node (ref "JP11") (pin "P$8") (pinfunction "8_P$8") (pintype "bidirectional"))
      (node (ref "JP21") (pin "P$8") (pinfunction "8_P$8") (pintype "bidirectional"))
      (node (ref "SJ4") (pin "2") (pinfunction "2_2") (pintype "passive"))
      (node (ref "U4") (pin "5") (pinfunction "+IN_5") (pintype "input"))
    )
    (net (code "25") (name "/LED1") (class "Default")
      (node (ref "IC8") (pin "20") (pinfunction "PB2/BOOT1_20") (pintype "bidirectional"))
      (node (ref "RN1") (pin "1") (pinfunction "1_1") (pintype "passive"))
    )
    (net (code "26") (name "/LED2") (class "Default")
      (node (ref "IC8") (pin "18") (pinfunction "PB0-ADC8/TIM3CH3_18") (pintype "bidirectional"))
      (node (ref "RN1") (pin "3") (pinfunction "1_3") (pintype "passive"))
    )
    (net (code "27") (name "/LED3") (class "Default")
      (node (ref "IC8") (pin "17") (pinfunction "PA7-SPI1MOSI/ADC7/TIM3CH2_17") (pintype "bidirectional"))
      (node (ref "RN1") (pin "5") (pinfunction "1_5") (pintype "passive"))
    )
    (net (code "28") (name "/LED4") (class "Default")
      (node (ref "IC8") (pin "25") (pinfunction "PB12-SPI2NSS/I2C2SMBAI/USART3CK_25") (pintype "bidirectional"))
      (node (ref "RN1") (pin "7") (pinfunction "1_7") (pintype "passive"))
    )
    (net (code "29") (name "/MOT_TEMP") (class "Default")
      (node (ref "IC8") (pin "14") (pinfunction "PA4-SPI1NSS/ADC4/USART2CK_14") (pintype "bidirectional"))
      (node (ref "JP12") (pin "P$8") (pinfunction "8_P$8") (pintype "bidirectional"))
      (node (ref "JP22") (pin "P$8") (pinfunction "8_P$8") (pintype "bidirectional"))
    )
    (net (code "30") (name "/NC") (class "Default")
      (node (ref "JP12") (pin "P$10") (pinfunction "10_P$10") (pintype "bidirectional"))
      (node (ref "JP22") (pin "P$10") (pinfunction "10_P$10") (pintype "bidirectional"))
    )
    (net (code "31") (name "/PHASE_A") (class "Default")
      (node (ref "ACS1") (pin "1") (pinfunction "IP+_1_1") (pintype "bidirectional"))
      (node (ref "ACS1") (pin "2") (pinfunction "IP+_2_2") (pintype "bidirectional"))
      (node (ref "C1") (pin "-") (pinfunction "-_-") (pintype "passive"))
      (node (ref "IC3") (pin "6") (pinfunction "VS_6") (pintype "bidirectional"))
      (node (ref "Q1") (pin "3") (pinfunction "S_3") (pintype "passive"))
      (node (ref "Q2") (pin "2") (pinfunction "D_2") (pintype "passive"))
      (node (ref "R17") (pin "1") (pinfunction "1_1") (pintype "passive"))
    )
    (net (code "32") (name "/PHASE_B") (class "Default")
      (node (ref "ACS2") (pin "1") (pinfunction "IP+_1_1") (pintype "bidirectional"))
      (node (ref "ACS2") (pin "2") (pinfunction "IP+_2_2") (pintype "bidirectional"))
      (node (ref "C2") (pin "-") (pinfunction "-_-") (pintype "passive"))
      (node (ref "IC4") (pin "6") (pinfunction "VS_6") (pintype "bidirectional"))
      (node (ref "Q3") (pin "3") (pinfunction "S_3") (pintype "passive"))
      (node (ref "Q4") (pin "2") (pinfunction "D_2") (pintype "passive"))
      (node (ref "R19") (pin "1") (pinfunction "1_1") (pintype "passive"))
    )
    (net (code "33") (name "/PHASE_C") (class "Default")
      (node (ref "ACS3") (pin "1") (pinfunction "IP+_1_1") (pintype "bidirectional"))
      (node (ref "ACS3") (pin "2") (pinfunction "IP+_2_2") (pintype "bidirectional"))
      (node (ref "C3") (pin "-") (pinfunction "-_-") (pintype "passive"))
      (node (ref "IC5") (pin "6") (pinfunction "VS_6") (pintype "bidirectional"))
      (node (ref "Q5") (pin "3") (pinfunction "S_3") (pintype "passive"))
      (node (ref "Q6") (pin "2") (pinfunction "D_2") (pintype "passive"))
      (node (ref "R21") (pin "1") (pinfunction "1_1") (pintype "passive"))
    )
    (net (code "34") (name "/PS_ID") (class "Default")
      (node (ref "IC8") (pin "16") (pinfunction "PA6-SPI1MISO/ADC6/TIM3CH1_16") (pintype "bidirectional"))
      (node (ref "JP12") (pin "P$5") (pinfunction "5_P$5") (pintype "bidirectional"))
      (node (ref "JP22") (pin "P$5") (pinfunction "5_P$5") (pintype "bidirectional"))
      (node (ref "R1") (pin "1") (pinfunction "1_1") (pintype "passive"))
      (node (ref "R2") (pin "2") (pinfunction "2_2") (pintype "passive"))
    )
    (net (code "35") (name "/RST") (class "Default")
      (node (ref "C14") (pin "2") (pinfunction "2_2") (pintype "passive"))
      (node (ref "IC8") (pin "7") (pinfunction "NRST_7") (pintype "bidirectional"))
      (node (ref "JTAG") (pin "P$3") (pinfunction "3_P$3") (pintype "bidirectional"))
      (node (ref "R13") (pin "1") (pinfunction "1_1") (pintype "passive"))
    )
    (net (code "36") (name "/RXD") (class "Default")
      (node (ref "IC8") (pin "22") (pinfunction "PB11-I2C2SDA/USART3RX_22") (pintype "bidirectional"))
      (node (ref "R3") (pin "2") (pinfunction "2_2") (pintype "passive"))
      (node (ref "R4") (pin "1") (pinfunction "1_1") (pintype "passive"))
    )
    (net (code "37") (name "/SCL") (class "Default")
      (node (ref "I2C") (pin "P$1") (pinfunction "1_P$1") (pintype "bidirectional"))
      (node (ref "IC8") (pin "42") (pinfunction "PB6-I2C1SCL/TIM4CH1-USART1TX_42") (pintype "bidirectional"))
    )
    (net (code "38") (name "/SDA") (class "Default")
      (node (ref "I2C") (pin "P$2") (pinfunction "2_P$2") (pintype "bidirectional"))
      (node (ref "IC8") (pin "43") (pinfunction "PB7-I2C1SDA/TIM4CH2-USART1RX_43") (pintype "bidirectional"))
    )
    (net (code "39") (name "/TCK") (class "Default")
      (node (ref "IC8") (pin "37") (pinfunction "PA14/JTCK/SWCLK_37") (pintype "bidirectional"))
      (node (ref "JTAG") (pin "P$7") (pinfunction "7_P$7") (pintype "bidirectional"))
      (node (ref "R9") (pin "2") (pinfunction "2_2") (pintype "passive"))
    )
    (net (code "40") (name "/TDI") (class "Default")
      (node (ref "IC8") (pin "38") (pinfunction "PA15/JTDI-TIM2CH1ETR/SPI1NSS_38") (pintype "bidirectional"))
      (node (ref "JTAG") (pin "P$1") (pinfunction "1_P$1") (pintype "bidirectional"))
      (node (ref "R14") (pin "1") (pinfunction "1_1") (pintype "passive"))
    )
    (net (code "41") (name "/TDO") (class "Default")
      (node (ref "IC8") (pin "39") (pinfunction "PB3/JTDO-TIM2CH2/SPI1SCK_39") (pintype "bidirectional"))
      (node (ref "JTAG") (pin "P$9") (pinfunction "9_P$9") (pintype "bidirectional"))
      (node (ref "R6") (pin "2") (pinfunction "2_2") (pintype "passive"))
    )
    (net (code "42") (name "/TEMP") (class "Default")
      (node (ref "IC8") (pin "15") (pinfunction "PA5-SPI1SCK/ADC5_15") (pintype "bidirectional"))
      (node (ref "JP12") (pin "P$7") (pinfunction "7_P$7") (pintype "bidirectional"))
      (node (ref "JP22") (pin "P$7") (pinfunction "7_P$7") (pintype "bidirectional"))
    )
    (net (code "43") (name "/TMS") (class "Default")
      (node (ref "IC8") (pin "34") (pinfunction "PA13/JTMS/SWDIO_34") (pintype "bidirectional"))
      (node (ref "JTAG") (pin "P$5") (pinfunction "5_P$5") (pintype "bidirectional"))
      (node (ref "R10") (pin "1") (pinfunction "1_1") (pintype "passive"))
    )
    (net (code "44") (name "/TRST") (class "Default")
      (node (ref "IC8") (pin "40") (pinfunction "PB4/JNTRST-TIM3CH1/SPI1MISO_40") (pintype "bidirectional"))
      (node (ref "JTAG") (pin "P$4") (pinfunction "4_P$4") (pintype "bidirectional"))
      (node (ref "R25") (pin "1") (pinfunction "1_1") (pintype "passive"))
    )
    (net (code "45") (name "/TXD") (class "Default")
      (node (ref "IC8") (pin "21") (pinfunction "PB10-I2C2SCL/USART3TX_21") (pintype "bidirectional"))
      (node (ref "R5") (pin "1") (pinfunction "1_1") (pintype "passive"))
    )
    (net (code "46") (name "/USB_+5V") (class "Default")
      (node (ref "D7") (pin "3") (pinfunction "A_3") (pintype "passive"))
      (node (ref "U3") (pin "PIN_1") (pinfunction "1_PIN_1") (pintype "input"))
    )
    (net (code "47") (name "/USB_DM") (class "Default")
      (node (ref "C18") (pin "1") (pinfunction "1_1") (pintype "passive"))
      (node (ref "IC8") (pin "32") (pinfunction "PA11-USART1CTS_32") (pintype "bidirectional"))
      (node (ref "R34") (pin "2") (pinfunction "2_2") (pintype "passive"))
    )
    (net (code "48") (name "/USB_DP") (class "Default")
      (node (ref "C17") (pin "1") (pinfunction "1_1") (pintype "passive"))
      (node (ref "IC8") (pin "33") (pinfunction "PA12-USART1RTS_33") (pintype "bidirectional"))
      (node (ref "R35") (pin "2") (pinfunction "2_2") (pintype "passive"))
    )
    (net (code "49") (name "/VBD") (class "Default")
      (node (ref "C24") (pin "+") (pinfunction "+_+") (pintype "passive"))
      (node (ref "C28") (pin "1") (pinfunction "1_1") (pintype "passive"))
      (node (ref "C29") (pin "1") (pinfunction "1_1") (pintype "passive"))
      (node (ref "C30") (pin "1") (pinfunction "1_1") (pintype "passive"))
      (node (ref "IC3") (pin "1") (pinfunction "VCC_1") (pintype "bidirectional"))
      (node (ref "IC4") (pin "1") (pinfunction "VCC_1") (pintype "bidirectional"))
      (node (ref "IC5") (pin "1") (pinfunction "VCC_1") (pintype "bidirectional"))
      (node (ref "SJ10") (pin "2") (pinfunction "2_2") (pintype "passive"))
    )
    (net (code "50") (name "/VBD_PUMP") (class "Default")
      (node (ref "C45") (pin "1") (pinfunction "1_1") (pintype "passive"))
      (node (ref "C46") (pin "+") (pinfunction "+_+") (pintype "passive"))
      (node (ref "IC7") (pin "6") (pinfunction "VOUT_6") (pintype "bidirectional"))
      (node (ref "SJ10") (pin "3") (pinfunction "3_3") (pintype "passive"))
    )
    (net (code "51") (name "/V_BATT") (class "Default")
      (node (ref "IC8") (pin "13") (pinfunction "PA3-USART2RX/ADC3/TIM2CH4_13") (pintype "bidirectional"))
      (node (ref "JP12") (pin "P$9") (pinfunction "9_P$9") (pintype "bidirectional"))
      (node (ref "JP22") (pin "P$9") (pinfunction "9_P$9") (pintype "bidirectional"))
      (node (ref "R26") (pin "1") (pinfunction "1_1") (pintype "passive"))
      (node (ref "R27") (pin "2") (pinfunction "2_2") (pintype "passive"))
    )
    (net (code "52") (name "GND") (class "Default")
      (node (ref "ACS1") (pin "5") (pinfunction "GND_5") (pintype "bidirectional"))
      (node (ref "ACS2") (pin "5") (pinfunction "GND_5") (pintype "bidirectional"))
      (node (ref "ACS3") (pin "5") (pinfunction "GND_5") (pintype "bidirectional"))
      (node (ref "ACS712") (pin "5") (pinfunction "GND_5") (pintype "bidirectional"))
      (node (ref "C10") (pin "2") (pinfunction "2_2") (pintype "passive"))
      (node (ref "C11") (pin "2") (pinfunction "2_2") (pintype "passive"))
      (node (ref "C12") (pin "1") (pinfunction "1_1") (pintype "passive"))
      (node (ref "C13") (pin "2") (pinfunction "2_2") (pintype "passive"))
      (node (ref "C14") (pin "1") (pinfunction "1_1") (pintype "passive"))
      (node (ref "C15") (pin "2") (pinfunction "2_2") (pintype "passive"))
      (node (ref "C16") (pin "2") (pinfunction "2_2") (pintype "passive"))
      (node (ref "C17") (pin "2") (pinfunction "2_2") (pintype "passive"))
      (node (ref "C18") (pin "2") (pinfunction "2_2") (pintype "passive"))
      (node (ref "C19") (pin "2") (pinfunction "2_2") (pintype "passive"))
      (node (ref "C20") (pin "2") (pinfunction "2_2") (pintype "passive"))
      (node (ref "C22") (pin "2") (pinfunction "2_2") (pintype "passive"))
      (node (ref "C23") (pin "2") (pinfunction "2_2") (pintype "passive"))
      (node (ref "C24") (pin "-") (pinfunction "-_-") (pintype "passive"))
      (node (ref "C25") (pin "2") (pinfunction "2_2") (pintype "passive"))
      (node (ref "C26") (pin "2") (pinfunction "2_2") (pintype "passive"))
      (node (ref "C28") (pin "2") (pinfunction "2_2") (pintype "passive"))
      (node (ref "C29") (pin "2") (pinfunction "2_2") (pintype "passive"))
      (node (ref "C30") (pin "2") (pinfunction "2_2") (pintype "passive"))
      (node (ref "C31") (pin "-") (pinfunction "-_-") (pintype "passive"))
      (node (ref "C32") (pin "1") (pinfunction "1_1") (pintype "passive"))
      (node (ref "C33") (pin "1") (pinfunction "1_1") (pintype "passive"))
      (node (ref "C34") (pin "1") (pinfunction "1_1") (pintype "passive"))
      (node (ref "C35") (pin "-") (pinfunction "-_-") (pintype "passive"))
      (node (ref "C36") (pin "2") (pinfunction "2_2") (pintype "passive"))
      (node (ref "C37") (pin "2") (pinfunction "2_2") (pintype "passive"))
      (node (ref "C38") (pin "-") (pinfunction "-_-") (pintype "passive"))
      (node (ref "C39") (pin "-") (pinfunction "-_-") (pintype "passive"))
      (node (ref "C4") (pin "2") (pinfunction "2_2") (pintype "passive"))
      (node (ref "C40") (pin "2") (pinfunction "2_2") (pintype "passive"))
      (node (ref "C41") (pin "-") (pinfunction "-_-") (pintype "passive"))
      (node (ref "C42") (pin "-") (pinfunction "-_-") (pintype "passive"))
      (node (ref "C46") (pin "-") (pinfunction "-_-") (pintype "passive"))
      (node (ref "C6") (pin "2") (pinfunction "2_2") (pintype "passive"))
      (node (ref "C7") (pin "-") (pinfunction "-_-") (pintype "passive"))
      (node (ref "C8") (pin "-") (pinfunction "-_-") (pintype "passive"))
      (node (ref "C9") (pin "2") (pinfunction "2_2") (pintype "passive"))
      (node (ref "D4") (pin "1") (pinfunction "A1_1") (pintype "passive"))
      (node (ref "D5") (pin "1") (pinfunction "A1_1") (pintype "passive"))
      (node (ref "D6") (pin "1") (pinfunction "A1_1") (pintype "passive"))
      (node (ref "I2C") (pin "P$3") (pinfunction "3_P$3") (pintype "bidirectional"))
      (node (ref "IC2") (pin "2") (pinfunction "GND_2") (pintype "bidirectional"))
      (node (ref "IC3") (pin "4") (pinfunction "COM_4") (pintype "bidirectional"))
      (node (ref "IC4") (pin "4") (pinfunction "COM_4") (pintype "bidirectional"))
      (node (ref "IC5") (pin "4") (pinfunction "COM_4") (pintype "bidirectional"))
      (node (ref "IC6") (pin "2") (pinfunction "GND_2") (pintype "power_in"))
      (node (ref "IC7") (pin "7") (pinfunction "GND_7") (pintype "bidirectional"))
      (node (ref "IC7") (pin "8") (pinfunction "SHDN_8") (pintype "bidirectional"))
      (node (ref "IC8") (pin "23") (pinfunction "VSS1_23") (pintype "power_in"))
      (node (ref "IC8") (pin "35") (pinfunction "VSS2_35") (pintype "power_in"))
      (node (ref "IC8") (pin "44") (pinfunction "BOOT0_44") (pintype "input"))
      (node (ref "IC8") (pin "47") (pinfunction "VSS3_47") (pintype "power_in"))
      (node (ref "IC8") (pin "8") (pinfunction "VSSA_8") (pintype "power_in"))
      (node (ref "JP11") (pin "P$1") (pinfunction "1_P$1") (pintype "bidirectional"))
      (node (ref "JP12") (pin "P$1") (pinfunction "1_P$1") (pintype "bidirectional"))
      (node (ref "JP21") (pin "P$1") (pinfunction "1_P$1") (pintype "bidirectional"))
      (node (ref "JP22") (pin "P$1") (pinfunction "1_P$1") (pintype "bidirectional"))
      (node (ref "JTAG") (pin "P$10") (pinfunction "10_P$10") (pintype "bidirectional"))
      (node (ref "JTAG") (pin "P$6") (pinfunction "6_P$6") (pintype "bidirectional"))
      (node (ref "JTAG") (pin "P$8") (pinfunction "8_P$8") (pintype "bidirectional"))
      (node (ref "PAD1") (pin "1") (pinfunction "P_1") (pintype "passive"))
      (node (ref "PAD7") (pin "1") (pinfunction "P_1") (pintype "passive"))
      (node (ref "Q2") (pin "3") (pinfunction "S_3") (pintype "passive"))
      (node (ref "Q4") (pin "3") (pinfunction "S_3") (pintype "passive"))
      (node (ref "Q6") (pin "3") (pinfunction "S_3") (pintype "passive"))
      (node (ref "Q7") (pin "2") (pinfunction "GND_2") (pintype "power_in"))
      (node (ref "R18") (pin "2") (pinfunction "2_2") (pintype "passive"))
      (node (ref "R2") (pin "1") (pinfunction "1_1") (pintype "passive"))
      (node (ref "R20") (pin "2") (pinfunction "2_2") (pintype "passive"))
      (node (ref "R22") (pin "2") (pinfunction "2_2") (pintype "passive"))
      (node (ref "R24") (pin "2") (pinfunction "2_2") (pintype "passive"))
      (node (ref "R27") (pin "1") (pinfunction "1_1") (pintype "passive"))
      (node (ref "R28") (pin "2") (pinfunction "2_2") (pintype "passive"))
      (node (ref "R29") (pin "2") (pinfunction "2_2") (pintype "passive"))
      (node (ref "R3") (pin "1") (pinfunction "1_1") (pintype "passive"))
      (node (ref "R30") (pin "2") (pinfunction "2_2") (pintype "passive"))
      (node (ref "R31") (pin "2") (pinfunction "2_2") (pintype "passive"))
      (node (ref "R32") (pin "2") (pinfunction "2_2") (pintype "passive"))
      (node (ref "R33") (pin "2") (pinfunction "2_2") (pintype "passive"))
      (node (ref "R42") (pin "2") (pinfunction "2_2") (pintype "passive"))
      (node (ref "R44") (pin "2") (pinfunction "2_2") (pintype "passive"))
      (node (ref "R46") (pin "2") (pinfunction "2_2") (pintype "passive"))
      (node (ref "U3") (pin "GND_LEFT") (pinfunction "S1_GND_LEFT") (pintype "passive"))
      (node (ref "U3") (pin "GND_RIGHT") (pinfunction "S2_GND_RIGHT") (pintype "passive"))
      (node (ref "U3") (pin "GND_UP_LEFT") (pinfunction "S3_GND_UP_LEFT") (pintype "passive"))
      (node (ref "U3") (pin "GND_UP_RIGHT") (pinfunction "S4_GND_UP_RIGHT") (pintype "passive"))
      (node (ref "U3") (pin "PIN_4") (pinfunction "4_PIN_4") (pintype "input"))
      (node (ref "U4") (pin "11") (pinfunction "V-_11") (pintype "power_in"))
      (node (ref "X-USART") (pin "1") (pinfunction "S_1") (pintype "passive"))
    )
    (net (code "53") (name "Net-(ACS1-FILTER)") (class "Default")
      (node (ref "ACS1") (pin "6") (pinfunction "FILTER_6") (pintype "bidirectional"))
      (node (ref "C20") (pin "1") (pinfunction "1_1") (pintype "passive"))
    )
    (net (code "54") (name "Net-(ACS1-IP-_1)") (class "Default")
      (node (ref "ACS1") (pin "3") (pinfunction "IP-_1_3") (pintype "bidirectional"))
      (node (ref "ACS1") (pin "4") (pinfunction "IP-_2_4") (pintype "bidirectional"))
      (node (ref "PAD3") (pin "1") (pinfunction "P_1") (pintype "passive"))
    )
    (net (code "55") (name "Net-(ACS1-VIOUT)") (class "Default")
      (node (ref "ACS1") (pin "7") (pinfunction "VIOUT_7") (pintype "bidirectional"))
      (node (ref "R41") (pin "2") (pinfunction "2_2") (pintype "passive"))
    )
    (net (code "56") (name "Net-(ACS2-FILTER)") (class "Default")
      (node (ref "ACS2") (pin "6") (pinfunction "FILTER_6") (pintype "bidirectional"))
      (node (ref "C23") (pin "1") (pinfunction "1_1") (pintype "passive"))
    )
    (net (code "57") (name "Net-(ACS2-IP-_1)") (class "Default")
      (node (ref "ACS2") (pin "3") (pinfunction "IP-_1_3") (pintype "bidirectional"))
      (node (ref "ACS2") (pin "4") (pinfunction "IP-_2_4") (pintype "bidirectional"))
      (node (ref "PAD4") (pin "1") (pinfunction "P_1") (pintype "passive"))
    )
    (net (code "58") (name "Net-(ACS2-VIOUT)") (class "Default")
      (node (ref "ACS2") (pin "7") (pinfunction "VIOUT_7") (pintype "bidirectional"))
      (node (ref "R43") (pin "2") (pinfunction "2_2") (pintype "passive"))
    )
    (net (code "59") (name "Net-(ACS3-FILTER)") (class "Default")
      (node (ref "ACS3") (pin "6") (pinfunction "FILTER_6") (pintype "bidirectional"))
      (node (ref "C26") (pin "1") (pinfunction "1_1") (pintype "passive"))
    )
    (net (code "60") (name "Net-(ACS3-IP-_1)") (class "Default")
      (node (ref "ACS3") (pin "3") (pinfunction "IP-_1_3") (pintype "bidirectional"))
      (node (ref "ACS3") (pin "4") (pinfunction "IP-_2_4") (pintype "bidirectional"))
      (node (ref "PAD5") (pin "1") (pinfunction "P_1") (pintype "passive"))
    )
    (net (code "61") (name "Net-(ACS3-VIOUT)") (class "Default")
      (node (ref "ACS3") (pin "7") (pinfunction "VIOUT_7") (pintype "bidirectional"))
      (node (ref "R45") (pin "2") (pinfunction "2_2") (pintype "passive"))
    )
    (net (code "62") (name "Net-(ACS712-FILTER)") (class "Default")
      (node (ref "ACS712") (pin "6") (pinfunction "FILTER_6") (pintype "bidirectional"))
      (node (ref "C11") (pin "1") (pinfunction "1_1") (pintype "passive"))
    )
    (net (code "63") (name "Net-(ACS712-VIOUT)") (class "Default")
      (node (ref "ACS712") (pin "7") (pinfunction "VIOUT_7") (pintype "bidirectional"))
      (node (ref "R23") (pin "2") (pinfunction "2_2") (pintype "passive"))
    )
    (net (code "64") (name "Net-(D1-C)") (class "Default")
      (node (ref "C1") (pin "+") (pinfunction "+_+") (pintype "passive"))
      (node (ref "D1") (pin "1") (pinfunction "C_1") (pintype "passive"))
      (node (ref "IC3") (pin "8") (pinfunction "VB_8") (pintype "bidirectional"))
    )
    (net (code "65") (name "Net-(D2-C)") (class "Default")
      (node (ref "C2") (pin "+") (pinfunction "+_+") (pintype "passive"))
      (node (ref "D2") (pin "1") (pinfunction "C_1") (pintype "passive"))
      (node (ref "IC4") (pin "8") (pinfunction "VB_8") (pintype "bidirectional"))
    )
    (net (code "66") (name "Net-(D3-C)") (class "Default")
      (node (ref "C3") (pin "+") (pinfunction "+_+") (pintype "passive"))
      (node (ref "D3") (pin "1") (pinfunction "C_1") (pintype "passive"))
      (node (ref "IC5") (pin "8") (pinfunction "VB_8") (pintype "bidirectional"))
    )
    (net (code "67") (name "Net-(IC2-BYPASS)") (class "Default")
      (node (ref "C4") (pin "1") (pinfunction "1_1") (pintype "passive"))
      (node (ref "IC2") (pin "4") (pinfunction "BYPASS_4") (pintype "bidirectional"))
    )
    (net (code "68") (name "Net-(IC3-HO)") (class "Default")
      (node (ref "IC3") (pin "7") (pinfunction "HO_7") (pintype "bidirectional"))
      (node (ref "R7") (pin "1") (pinfunction "1_1") (pintype "passive"))
    )
    (net (code "69") (name "Net-(IC3-LO)") (class "Default")
      (node (ref "IC3") (pin "5") (pinfunction "LO_5") (pintype "bidirectional"))
      (node (ref "R8") (pin "1") (pinfunction "1_1") (pintype "passive"))
    )
    (net (code "70") (name "Net-(IC4-HO)") (class "Default")
      (node (ref "IC4") (pin "7") (pinfunction "HO_7") (pintype "bidirectional"))
      (node (ref "R11") (pin "1") (pinfunction "1_1") (pintype "passive"))
    )
    (net (code "71") (name "Net-(IC4-LO)") (class "Default")
      (node (ref "IC4") (pin "5") (pinfunction "LO_5") (pintype "bidirectional"))
      (node (ref "R12") (pin "1") (pinfunction "1_1") (pintype "passive"))
    )
    (net (code "72") (name "Net-(IC5-HO)") (class "Default")
      (node (ref "IC5") (pin "7") (pinfunction "HO_7") (pintype "bidirectional"))
      (node (ref "R15") (pin "1") (pinfunction "1_1") (pintype "passive"))
    )
    (net (code "73") (name "Net-(IC5-LO)") (class "Default")
      (node (ref "IC5") (pin "5") (pinfunction "LO_5") (pintype "bidirectional"))
      (node (ref "R16") (pin "1") (pinfunction "1_1") (pintype "passive"))
    )
    (net (code "74") (name "Net-(IC7-C1+)") (class "Default")
      (node (ref "C43") (pin "1") (pinfunction "1_1") (pintype "passive"))
      (node (ref "IC7") (pin "2") (pinfunction "C1+_2") (pintype "bidirectional"))
    )
    (net (code "75") (name "Net-(IC7-C1-)") (class "Default")
      (node (ref "C43") (pin "2") (pinfunction "2_2") (pintype "passive"))
      (node (ref "IC7") (pin "1") (pinfunction "C1-_1") (pintype "bidirectional"))
    )
    (net (code "76") (name "Net-(IC7-C2+)") (class "Default")
      (node (ref "C44") (pin "1") (pinfunction "1_1") (pintype "passive"))
      (node (ref "IC7") (pin "4") (pinfunction "C2+_4") (pintype "bidirectional"))
    )
    (net (code "77") (name "Net-(IC7-C2-)") (class "Default")
      (node (ref "C44") (pin "2") (pinfunction "2_2") (pintype "passive"))
      (node (ref "IC7") (pin "3") (pinfunction "C2-_3") (pintype "bidirectional"))
    )
    (net (code "78") (name "Net-(IC8-PA8-USART1CK{slash}MCO)") (class "Default")
      (node (ref "IC8") (pin "29") (pinfunction "PA8-USART1CK/MCO_29") (pintype "bidirectional"))
      (node (ref "R40") (pin "2") (pinfunction "2_2") (pintype "passive"))
    )
    (net (code "79") (name "Net-(IC8-PA9-USART1TX)") (class "Default")
      (node (ref "IC8") (pin "30") (pinfunction "PA9-USART1TX_30") (pintype "bidirectional"))
      (node (ref "R47") (pin "2") (pinfunction "2_2") (pintype "passive"))
    )
    (net (code "80") (name "Net-(IC8-PA10-USART1RX)") (class "Default")
      (node (ref "IC8") (pin "31") (pinfunction "PA10-USART1RX_31") (pintype "bidirectional"))
      (node (ref "R48") (pin "2") (pinfunction "2_2") (pintype "passive"))
    )
    (net (code "81") (name "Net-(IC8-PB13-SPI2SCK{slash}USART3CTS)") (class "Default")
      (node (ref "IC8") (pin "26") (pinfunction "PB13-SPI2SCK/USART3CTS_26") (pintype "bidirectional"))
      (node (ref "R37") (pin "1") (pinfunction "1_1") (pintype "passive"))
    )
    (net (code "82") (name "Net-(IC8-PB14-SPI2MISO{slash}USART3RTS)") (class "Default")
      (node (ref "IC8") (pin "27") (pinfunction "PB14-SPI2MISO/USART3RTS_27") (pintype "bidirectional"))
      (node (ref "R38") (pin "1") (pinfunction "1_1") (pintype "passive"))
    )
    (net (code "83") (name "Net-(IC8-PB15-SPI2MOSI)") (class "Default")
      (node (ref "IC8") (pin "28") (pinfunction "PB15-SPI2MOSI_28") (pintype "bidirectional"))
      (node (ref "R39") (pin "1") (pinfunction "1_1") (pintype "passive"))
    )
    (net (code "84") (name "Net-(IC8-PD0-OSC_IN)") (class "Default")
      (node (ref "IC8") (pin "5") (pinfunction "PD0-OSC_IN_5") (pintype "input"))
      (node (ref "Q7") (pin "3") (pinfunction "OUT_3") (pintype "output"))
    )
    (net (code "85") (name "Net-(LED1-PadC)") (class "Default")
      (node (ref "LED1") (pin "C") (pinfunction "C_C") (pintype "passive"))
      (node (ref "RN1") (pin "2") (pinfunction "2_2") (pintype "passive"))
    )
    (net (code "86") (name "Net-(LED5A-C)") (class "Default")
      (node (ref "LED5") (pin "C3") (pinfunction "C_C3") (pintype "passive"))
      (node (ref "RN1") (pin "6") (pinfunction "2_6") (pintype "passive"))
    )
    (net (code "87") (name "Net-(LED5B-C)") (class "Default")
      (node (ref "LED5") (pin "C2") (pinfunction "C_C2") (pintype "passive"))
      (node (ref "RN1") (pin "4") (pinfunction "2_4") (pintype "passive"))
    )
    (net (code "88") (name "Net-(LED5C-C)") (class "Default")
      (node (ref "LED5") (pin "C1") (pinfunction "C_C1") (pintype "passive"))
      (node (ref "RN1") (pin "8") (pinfunction "2_8") (pintype "passive"))
    )
    (net (code "89") (name "Net-(Q1-G)") (class "Default")
      (node (ref "Q1") (pin "1") (pinfunction "G_1") (pintype "passive"))
      (node (ref "R7") (pin "2") (pinfunction "2_2") (pintype "passive"))
    )
    (net (code "90") (name "Net-(Q2-G)") (class "Default")
      (node (ref "Q2") (pin "1") (pinfunction "G_1") (pintype "passive"))
      (node (ref "R8") (pin "2") (pinfunction "2_2") (pintype "passive"))
    )
    (net (code "91") (name "Net-(Q3-G)") (class "Default")
      (node (ref "Q3") (pin "1") (pinfunction "G_1") (pintype "passive"))
      (node (ref "R11") (pin "2") (pinfunction "2_2") (pintype "passive"))
    )
    (net (code "92") (name "Net-(Q4-G)") (class "Default")
      (node (ref "Q4") (pin "1") (pinfunction "G_1") (pintype "passive"))
      (node (ref "R12") (pin "2") (pinfunction "2_2") (pintype "passive"))
    )
    (net (code "93") (name "Net-(Q5-G)") (class "Default")
      (node (ref "Q5") (pin "1") (pinfunction "G_1") (pintype "passive"))
      (node (ref "R15") (pin "2") (pinfunction "2_2") (pintype "passive"))
    )
    (net (code "94") (name "Net-(Q6-G)") (class "Default")
      (node (ref "Q6") (pin "1") (pinfunction "G_1") (pintype "passive"))
      (node (ref "R16") (pin "2") (pinfunction "2_2") (pintype "passive"))
    )
    (net (code "95") (name "Net-(U3-2)") (class "Default")
      (node (ref "R34") (pin "1") (pinfunction "1_1") (pintype "passive"))
      (node (ref "U3") (pin "PIN_2") (pinfunction "2_PIN_2") (pintype "input"))
    )
    (net (code "96") (name "Net-(U3-3)") (class "Default")
      (node (ref "R35") (pin "1") (pinfunction "1_1") (pintype "passive"))
      (node (ref "R36") (pin "2") (pinfunction "2_2") (pintype "passive"))
      (node (ref "U3") (pin "PIN_3") (pinfunction "3_PIN_3") (pintype "input"))
    )
    (net (code "97") (name "Net-(U3-5)") (class "Default")
      (node (ref "SJ1") (pin "2") (pinfunction "2_2") (pintype "passive"))
      (node (ref "U3") (pin "PIN_5") (pinfunction "5_PIN_5") (pintype "input"))
    )
    (net (code "98") (name "Net-(X-USARTB-S)") (class "Default")
      (node (ref "R4") (pin "2") (pinfunction "2_2") (pintype "passive"))
      (node (ref "X-USART") (pin "2") (pinfunction "S_2") (pintype "passive"))
    )
    (net (code "99") (name "Net-(X-USARTC-S)") (class "Default")
      (node (ref "R5") (pin "2") (pinfunction "2_2") (pintype "passive"))
      (node (ref "X-USART") (pin "3") (pinfunction "S_3") (pintype "passive"))
    )
    (net (code "100") (name "Net-(X-USARTD-S)") (class "Default")
      (node (ref "SJ5") (pin "2") (pinfunction "2_2") (pintype "passive"))
      (node (ref "X-USART") (pin "4") (pinfunction "S_4") (pintype "passive"))
    )
    (net (code "101") (name "unconnected-(IC8-PB5-I2C1SMBAI-TIM3CH2{slash}SPI1MOSI-Pad41)") (class "Default")
      (node (ref "IC8") (pin "41") (pinfunction "PB5-I2C1SMBAI-TIM3CH2/SPI1MOSI_41") (pintype "bidirectional"))
    )
    (net (code "102") (name "unconnected-(IC8-PB8-TIM4CH3-I2C1SCL-Pad45)") (class "Default")
      (node (ref "IC8") (pin "45") (pinfunction "PB8-TIM4CH3-I2C1SCL_45") (pintype "bidirectional"))
    )
    (net (code "103") (name "unconnected-(IC8-PB9-TIM4CH4-I2C1SDA-Pad46)") (class "Default")
      (node (ref "IC8") (pin "46") (pinfunction "PB9-TIM4CH4-I2C1SDA_46") (pintype "bidirectional"))
    )
    (net (code "104") (name "unconnected-(IC8-PC13-TAMPER-RTC-Pad2)") (class "Default")
      (node (ref "IC8") (pin "2") (pinfunction "PC13-TAMPER-RTC_2") (pintype "bidirectional"))
    )
    (net (code "105") (name "unconnected-(IC8-PC14-OSC32_IN-Pad3)") (class "Default")
      (node (ref "IC8") (pin "3") (pinfunction "PC14-OSC32_IN_3") (pintype "bidirectional"))
    )
    (net (code "106") (name "unconnected-(IC8-PC15-OSC32_OUT-Pad4)") (class "Default")
      (node (ref "IC8") (pin "4") (pinfunction "PC15-OSC32_OUT_4") (pintype "bidirectional"))
    )
    (net (code "107") (name "unconnected-(IC8-PD1-OSC_OUT-Pad6)") (class "Default")
      (node (ref "IC8") (pin "6") (pinfunction "PD1-OSC_OUT_6") (pintype "output"))
    )
    (net (code "108") (name "unconnected-(Q7-TRI-Pad1)") (class "Default")
      (node (ref "Q7") (pin "1") (pinfunction "TRI_1") (pintype "output"))
    )
  )
)
